# DELA_EPROMMER_II.net
KiCad netlist of a schematic drawn in Altium Designer
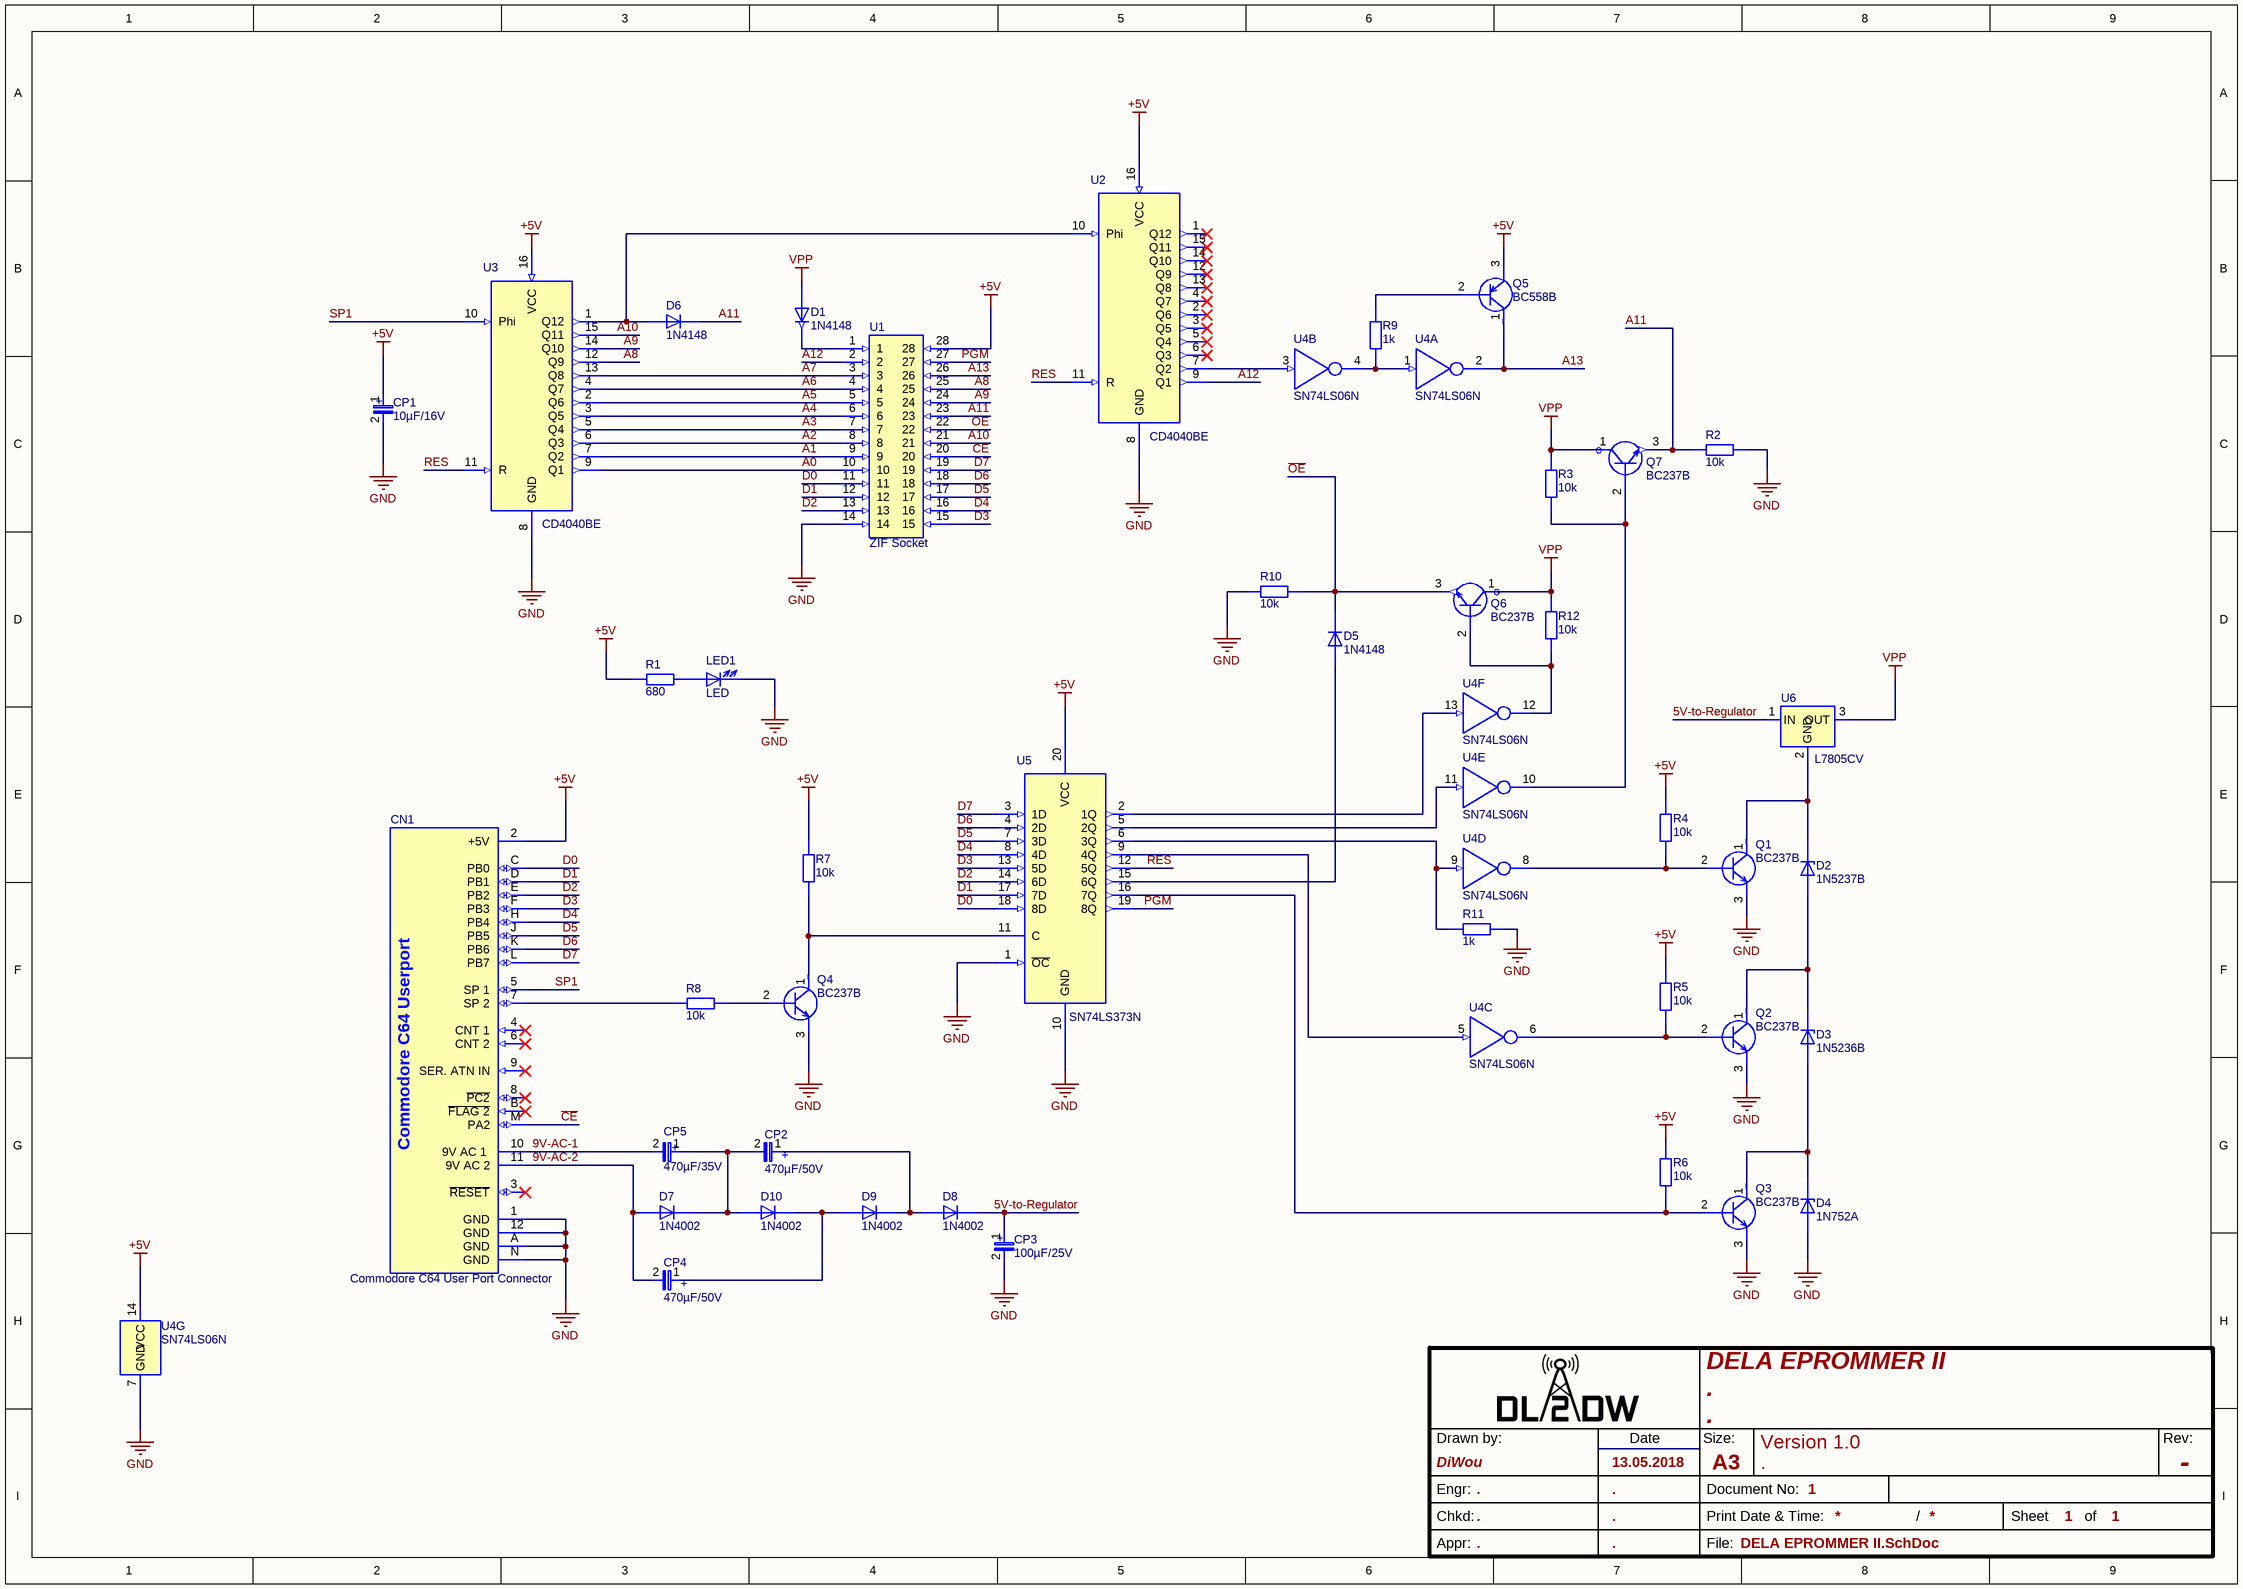
[diagram p0: DELA EPROMMER II.SchDoc]

(export (version "E")
  (design (tool "Eeschema 10.0.6"))
  (components
    (comp (ref "CN1")
      (value "Commodore C64 User Port Connector")
      (footprint "C64 User Port Connector")
      (description "Connector for soldering on the board, for connection to the user port of the C64.")
      (libsource (lib "PCB-Tech Cloud") (part "C64 Userport"))
    )
    (comp (ref "CP1")
      (value "10µF/16V")
      (footprint "CAP Elec 10µF 16V RND 150EHR100M16B")
      (description "RND 150EHR100M16B - Kondensator, 10µF, 16V, 20%, RND Components")
      (libsource (lib "") (part "Polarized Capacitor_2"))
    )
    (comp (ref "CP2")
      (value "470µF/50V")
      (footprint "CAP Elec. 470µF 50V Panasonic ECA1HHG471")
      (description "Capacitor 470 uF 50 VDC, ECA1HHG471, Panasonic Automotive & Industrial Systems")
      (fields (field (name "VOLTAGE") "50V") (field (name "TOLERANCE") "20%"))
      (libsource (lib "PCB-Tech Cloud") (part "Polarized Capacitor"))
    )
    (comp (ref "CP3")
      (value "100µF/25V")
      (footprint "CAP Elec 100µF 25V Panasonic ECA1EHG101")
      (description "Capacitor 100 uF 25 VDC, ECA1EHG101, Panasonic Automotive & Industrial Systems")
      (fields (field (name "TOLERANCE") "20%") (field (name "VOLTAGE") "25V"))
      (libsource (lib "") (part "Polarized Capacitor_2"))
    )
    (comp (ref "CP4")
      (value "470µF/50V")
      (footprint "CAP Elec. 470µF 50V Panasonic ECA1HHG471")
      (description "Capacitor 470 uF 50 VDC, ECA1HHG471, Panasonic Automotive & Industrial Systems")
      (fields (field (name "VOLTAGE") "50V") (field (name "TOLERANCE") "20%"))
      (libsource (lib "PCB-Tech Cloud") (part "Polarized Capacitor"))
    )
    (comp (ref "CP5")
      (value "470µF/35V")
      (footprint "CAP Elec 470µF 35V Panasonic ECA1VHG471")
      (fields (field (name "TOLERANCE") "20%") (field (name "VOLTAGE") "35V"))
      (libsource (lib "") (part "Polarized Capacitor_1"))
    )
    (comp (ref "D1")
      (value "1N4148")
      (footprint "1N4148 P=5.08mm")
      (description "NEXPERIA - 1N4148 - DIODE, 1N4148 AMMO-BOX 10K")
      (fields (field (name "VOLTAGE") "100V"))
      (libsource (lib "PCB-Tech Cloud") (part "Diode Standard"))
    )
    (comp (ref "D2")
      (value "1N5237B")
      (footprint "1N5237B  P=5.08mm")
      (fields (field (name "TOLERANCE") "5%"))
      (libsource (lib "PCB-Tech Cloud") (part "Zener Diode"))
    )
    (comp (ref "D3")
      (value "1N5236B")
      (footprint "1N5236B  P=5.08mm")
      (fields (field (name "TOLERANCE") "5%"))
      (libsource (lib "PCB-Tech Cloud") (part "Zener Diode"))
    )
    (comp (ref "D4")
      (value "1N752A")
      (footprint "1N752A P=5.08mm")
      (description "Zener Diode 5.6V 1/2 Watt 5% Do-35 Case")
      (libsource (lib "PCB-Tech Cloud") (part "Zener Diode"))
    )
    (comp (ref "D5")
      (value "1N4148")
      (footprint "1N4148 P=5.08mm")
      (description "NEXPERIA - 1N4148 - DIODE, 1N4148 AMMO-BOX 10K")
      (fields (field (name "VOLTAGE") "100V"))
      (libsource (lib "PCB-Tech Cloud") (part "Diode Standard"))
    )
    (comp (ref "D6")
      (value "1N4148")
      (footprint "1N4148 P=5.08mm")
      (description "NEXPERIA - 1N4148 - DIODE, 1N4148 AMMO-BOX 10K")
      (fields (field (name "VOLTAGE") "100V"))
      (libsource (lib "PCB-Tech Cloud") (part "Diode Standard"))
    )
    (comp (ref "D7")
      (value "1N4002")
      (footprint "1N4002 P=7.62mm")
      (description "DIODE GEN PURP 100V 1A DO41")
      (libsource (lib "PCB-Tech Cloud") (part "Diode Standard"))
    )
    (comp (ref "D8")
      (value "1N4002")
      (footprint "1N4002 P=7.62mm")
      (description "DIODE GEN PURP 100V 1A DO41")
      (libsource (lib "PCB-Tech Cloud") (part "Diode Standard"))
    )
    (comp (ref "D9")
      (value "1N4002")
      (footprint "1N4002 P=7.62mm")
      (description "DIODE GEN PURP 100V 1A DO41")
      (libsource (lib "PCB-Tech Cloud") (part "Diode Standard"))
    )
    (comp (ref "D10")
      (value "1N4002")
      (footprint "1N4002 P=7.62mm")
      (description "DIODE GEN PURP 100V 1A DO41")
      (libsource (lib "PCB-Tech Cloud") (part "Diode Standard"))
    )
    (comp (ref "LED1")
      (value "LED")
      (footprint "LED 3mm Red Straight")
      (description "WURTH ELEKTRONIK   151033RS03000   LED, 3MM,  RED, 2600MCD, 621NM")
      (libsource (lib "PCB-Tech Cloud") (part "LED Standard"))
    )
    (comp (ref "Q1")
      (value "BC237B")
      (footprint "BC237")
      (libsource (lib "PCB-Tech Cloud") (part "Transistor NPN CBE"))
    )
    (comp (ref "Q2")
      (value "BC237B")
      (footprint "BC237")
      (libsource (lib "PCB-Tech Cloud") (part "Transistor NPN CBE"))
    )
    (comp (ref "Q3")
      (value "BC237B")
      (footprint "BC237")
      (libsource (lib "PCB-Tech Cloud") (part "Transistor NPN CBE"))
    )
    (comp (ref "Q4")
      (value "BC237B")
      (footprint "BC237")
      (libsource (lib "PCB-Tech Cloud") (part "Transistor NPN CBE"))
    )
    (comp (ref "Q5")
      (value "BC558B")
      (footprint "BC558B")
      (libsource (lib "PCB-Tech Cloud") (part "Transistor PNP CBE"))
    )
    (comp (ref "Q6")
      (value "BC237B")
      (footprint "BC237")
      (libsource (lib "PCB-Tech Cloud") (part "Transistor NPN CBE"))
    )
    (comp (ref "Q7")
      (value "BC237B")
      (footprint "BC237")
      (libsource (lib "PCB-Tech Cloud") (part "Transistor NPN CBE"))
    )
    (comp (ref "R1")
      (value "680")
      (footprint "680 kOhm R Axial DIN0207 L6.3mm D2.5mm P7.62mm Horizontal")
      (description "Res 680K Ohm 1/4W 5% Axial")
      (fields (field (name "TOLERANCE") "5%"))
      (libsource (lib "PCB-Tech Cloud") (part "Resistor"))
    )
    (comp (ref "R2")
      (value "10k")
      (footprint "10 kOhm R Axial DIN0207 L6.3mm D2.5mm P7.62mm Horizontal")
      (description "RES 10K OHM 1/4W 5% AXIAL")
      (fields (field (name "TOLERANCE") "5%"))
      (libsource (lib "PCB-Tech Cloud") (part "Resistor"))
    )
    (comp (ref "R3")
      (value "10k")
      (footprint "10 kOhm R Axial DIN0207 L6.3mm D2.5mm P7.62mm Horizontal")
      (description "RES 10K OHM 1/4W 5% AXIAL")
      (fields (field (name "TOLERANCE") "5%"))
      (libsource (lib "PCB-Tech Cloud") (part "Resistor"))
    )
    (comp (ref "R4")
      (value "10k")
      (footprint "10 kOhm R Axial DIN0207 L6.3mm D2.5mm P7.62mm Horizontal")
      (description "RES 10K OHM 1/4W 5% AXIAL")
      (fields (field (name "TOLERANCE") "5%"))
      (libsource (lib "PCB-Tech Cloud") (part "Resistor"))
    )
    (comp (ref "R5")
      (value "10k")
      (footprint "10 kOhm R Axial DIN0207 L6.3mm D2.5mm P7.62mm Horizontal")
      (description "RES 10K OHM 1/4W 5% AXIAL")
      (fields (field (name "TOLERANCE") "5%"))
      (libsource (lib "PCB-Tech Cloud") (part "Resistor"))
    )
    (comp (ref "R6")
      (value "10k")
      (footprint "10 kOhm R Axial DIN0207 L6.3mm D2.5mm P7.62mm Horizontal")
      (description "RES 10K OHM 1/4W 5% AXIAL")
      (fields (field (name "TOLERANCE") "5%"))
      (libsource (lib "PCB-Tech Cloud") (part "Resistor"))
    )
    (comp (ref "R7")
      (value "10k")
      (footprint "10 kOhm R Axial DIN0207 L6.3mm D2.5mm P7.62mm Horizontal")
      (description "RES 10K OHM 1/4W 5% AXIAL")
      (fields (field (name "TOLERANCE") "5%"))
      (libsource (lib "PCB-Tech Cloud") (part "Resistor"))
    )
    (comp (ref "R8")
      (value "10k")
      (footprint "10 kOhm R Axial DIN0207 L6.3mm D2.5mm P7.62mm Horizontal")
      (description "RES 10K OHM 1/4W 5% AXIAL")
      (fields (field (name "TOLERANCE") "5%"))
      (libsource (lib "PCB-Tech Cloud") (part "Resistor"))
    )
    (comp (ref "R9")
      (value "1k")
      (footprint "1,0 kOhm R Axial DIN0207 L6.3mm D2.5mm P7.62mm Horizontal")
      (description "RES 1K OHM 1/4W 5% AXIAL")
      (fields (field (name "TOLERANCE") "5%"))
      (libsource (lib "PCB-Tech Cloud") (part "Resistor"))
    )
    (comp (ref "R10")
      (value "10k")
      (footprint "10 kOhm R Axial DIN0207 L6.3mm D2.5mm P7.62mm Horizontal")
      (description "RES 10K OHM 1/4W 5% AXIAL")
      (fields (field (name "TOLERANCE") "5%"))
      (libsource (lib "PCB-Tech Cloud") (part "Resistor"))
    )
    (comp (ref "R11")
      (value "1k")
      (footprint "1,0 kOhm R Axial DIN0207 L6.3mm D2.5mm P7.62mm Horizontal")
      (description "RES 1K OHM 1/4W 5% AXIAL")
      (fields (field (name "TOLERANCE") "5%"))
      (libsource (lib "PCB-Tech Cloud") (part "Resistor"))
    )
    (comp (ref "R12")
      (value "10k")
      (footprint "10 kOhm R Axial DIN0207 L6.3mm D2.5mm P7.62mm Horizontal")
      (description "RES 10K OHM 1/4W 5% AXIAL")
      (fields (field (name "TOLERANCE") "5%"))
      (libsource (lib "PCB-Tech Cloud") (part "Resistor"))
    )
    (comp (ref "U1")
      (value "ZIF Socket")
      (footprint "ZIF Socket Textool 28pos P=15.24mm")
      (description "CONN IC DIP SOCKET ZIF 28POS GLD")
      (libsource (lib "PCB-Tech Cloud") (part "ZIF Socket Textool 28pos"))
    )
    (comp (ref "U2")
      (value "CD4040BE")
      (footprint "CD4040BE with Socket")
      (description "Counter/Divider Single 12-Bit Binary UP 16-Pin PDIP Tube")
      (libsource (lib "PCB-Tech Cloud") (part "CD4040BE"))
    )
    (comp (ref "U3")
      (value "CD4040BE")
      (footprint "CD4040BE with Socket")
      (description "Counter/Divider Single 12-Bit Binary UP 16-Pin PDIP Tube")
      (libsource (lib "PCB-Tech Cloud") (part "CD4040BE"))
    )
    (comp (ref "U4")
      (value "SN74LS06N")
      (footprint "SN74LS06N with Socket")
      (description "IC INVERTER OPEN COL 6CH 14DIP")
      (libsource (lib "") (part "74xx06_1"))
    )
    (comp (ref "U5")
      (value "SN74LS373N")
      (footprint "SN74LS373N with Socket")
      (description "Latch Transparent 3-ST 8-CH D-Type 20-Pin PDIP Tube")
      (libsource (lib "PCB-Tech Cloud") (part "74xx373"))
    )
    (comp (ref "U6")
      (value "L7805CV")
      (footprint "L 7805 CV")
      (description "STMICROELECTRONICS - L7806CV - LINEAR VOLTAGE REGULATOR 6V TO-220-3")
      (fields (field (name "TOLERANCE") "5%"))
      (libsource (lib "PCB-Tech Cloud") (part "L7805CV"))
    )
  )
  (nets
    (net (code "1") (name "+5V") (class "Default")
      (node (ref "CN1") (pin "2") (pinfunction "+5V_2") (pintype "power_in"))
      (node (ref "CP1") (pin "1") (pinfunction "1_1") (pintype "passive"))
      (node (ref "Q5") (pin "3") (pinfunction "3_3") (pintype "passive"))
      (node (ref "R1") (pin "2") (pinfunction "2_2") (pintype "passive"))
      (node (ref "R4") (pin "1") (pinfunction "1_1") (pintype "passive"))
      (node (ref "R5") (pin "1") (pinfunction "1_1") (pintype "passive"))
      (node (ref "R6") (pin "1") (pinfunction "1_1") (pintype "passive"))
      (node (ref "R7") (pin "1") (pinfunction "1_1") (pintype "passive"))
      (node (ref "U1") (pin "28") (pinfunction "28_28") (pintype "input"))
      (node (ref "U2") (pin "16") (pinfunction "VCC_16") (pintype "input"))
      (node (ref "U3") (pin "16") (pinfunction "VCC_16") (pintype "input"))
      (node (ref "U4") (pin "14") (pinfunction "VCC_14") (pintype "power_in"))
      (node (ref "U5") (pin "20") (pinfunction "VCC_20") (pintype "power_in"))
    )
    (net (code "2") (name "/5V-to-Regulator") (class "Default")
      (node (ref "CP3") (pin "1") (pinfunction "1_1") (pintype "passive"))
      (node (ref "D8") (pin "1") (pinfunction "1_1") (pintype "passive"))
      (node (ref "U6") (pin "1") (pinfunction "IN_1") (pintype "power_in"))
    )
    (net (code "3") (name "/9V-AC-1") (class "Default")
      (node (ref "CN1") (pin "10") (pinfunction "9V_AC_1_10") (pintype "power_in"))
      (node (ref "CP5") (pin "2") (pinfunction "2_2") (pintype "passive"))
    )
    (net (code "4") (name "/9V-AC-2") (class "Default")
      (node (ref "CN1") (pin "11") (pinfunction "9V_AC_2_11") (pintype "power_in"))
      (node (ref "CP4") (pin "2") (pinfunction "2_2") (pintype "passive"))
      (node (ref "D7") (pin "2") (pinfunction "2_2") (pintype "passive"))
    )
    (net (code "5") (name "/A0") (class "Default")
      (node (ref "U1") (pin "10") (pinfunction "10_10") (pintype "input"))
      (node (ref "U3") (pin "9") (pinfunction "Q1_9") (pintype "output"))
    )
    (net (code "6") (name "/A1") (class "Default")
      (node (ref "U1") (pin "9") (pinfunction "9_9") (pintype "input"))
      (node (ref "U3") (pin "7") (pinfunction "Q2_7") (pintype "output"))
    )
    (net (code "7") (name "/A2") (class "Default")
      (node (ref "U1") (pin "8") (pinfunction "8_8") (pintype "input"))
      (node (ref "U3") (pin "6") (pinfunction "Q3_6") (pintype "output"))
    )
    (net (code "8") (name "/A3") (class "Default")
      (node (ref "U1") (pin "7") (pinfunction "7_7") (pintype "input"))
      (node (ref "U3") (pin "5") (pinfunction "Q4_5") (pintype "output"))
    )
    (net (code "9") (name "/A4") (class "Default")
      (node (ref "U1") (pin "6") (pinfunction "6_6") (pintype "input"))
      (node (ref "U3") (pin "3") (pinfunction "Q5_3") (pintype "output"))
    )
    (net (code "10") (name "/A5") (class "Default")
      (node (ref "U1") (pin "5") (pinfunction "5_5") (pintype "input"))
      (node (ref "U3") (pin "2") (pinfunction "Q6_2") (pintype "output"))
    )
    (net (code "11") (name "/A6") (class "Default")
      (node (ref "U1") (pin "4") (pinfunction "4_4") (pintype "input"))
      (node (ref "U3") (pin "4") (pinfunction "Q7_4") (pintype "output"))
    )
    (net (code "12") (name "/A7") (class "Default")
      (node (ref "U1") (pin "3") (pinfunction "3_3") (pintype "input"))
      (node (ref "U3") (pin "13") (pinfunction "Q8_13") (pintype "output"))
    )
    (net (code "13") (name "/A8") (class "Default")
      (node (ref "U1") (pin "25") (pinfunction "25_25") (pintype "input"))
      (node (ref "U3") (pin "12") (pinfunction "Q9_12") (pintype "output"))
    )
    (net (code "14") (name "/A9") (class "Default")
      (node (ref "U1") (pin "24") (pinfunction "24_24") (pintype "input"))
      (node (ref "U3") (pin "14") (pinfunction "Q10_14") (pintype "output"))
    )
    (net (code "15") (name "/A10") (class "Default")
      (node (ref "U1") (pin "21") (pinfunction "21_21") (pintype "input"))
      (node (ref "U3") (pin "15") (pinfunction "Q11_15") (pintype "output"))
    )
    (net (code "16") (name "/A11") (class "Default")
      (node (ref "D6") (pin "1") (pinfunction "1_1") (pintype "passive"))
      (node (ref "Q7") (pin "3") (pinfunction "3_3") (pintype "passive"))
      (node (ref "R2") (pin "2") (pinfunction "2_2") (pintype "passive"))
      (node (ref "U1") (pin "23") (pinfunction "23_23") (pintype "input"))
    )
    (net (code "17") (name "/A12") (class "Default")
      (node (ref "U1") (pin "2") (pinfunction "2_2") (pintype "input"))
      (node (ref "U2") (pin "9") (pinfunction "Q1_9") (pintype "output"))
    )
    (net (code "18") (name "/A13") (class "Default")
      (node (ref "Q5") (pin "1") (pinfunction "1_1") (pintype "passive"))
      (node (ref "U1") (pin "26") (pinfunction "26_26") (pintype "input"))
      (node (ref "U4") (pin "2") (pinfunction "1Y_2") (pintype "open_collector"))
    )
    (net (code "19") (name "/D0") (class "Default")
      (node (ref "CN1") (pin "C") (pinfunction "PB0_C") (pintype "bidirectional"))
      (node (ref "U1") (pin "11") (pinfunction "11_11") (pintype "input"))
      (node (ref "U5") (pin "18") (pinfunction "8D_18") (pintype "input"))
    )
    (net (code "20") (name "/D1") (class "Default")
      (node (ref "CN1") (pin "D") (pinfunction "PB1_D") (pintype "bidirectional"))
      (node (ref "U1") (pin "12") (pinfunction "12_12") (pintype "input"))
      (node (ref "U5") (pin "17") (pinfunction "7D_17") (pintype "input"))
    )
    (net (code "21") (name "/D2") (class "Default")
      (node (ref "CN1") (pin "E") (pinfunction "PB2_E") (pintype "bidirectional"))
      (node (ref "U1") (pin "13") (pinfunction "13_13") (pintype "input"))
      (node (ref "U5") (pin "14") (pinfunction "6D_14") (pintype "input"))
    )
    (net (code "22") (name "/D3") (class "Default")
      (node (ref "CN1") (pin "F") (pinfunction "PB3_F") (pintype "bidirectional"))
      (node (ref "U1") (pin "15") (pinfunction "15_15") (pintype "input"))
      (node (ref "U5") (pin "13") (pinfunction "5D_13") (pintype "input"))
    )
    (net (code "23") (name "/D4") (class "Default")
      (node (ref "CN1") (pin "H") (pinfunction "PB4_H") (pintype "bidirectional"))
      (node (ref "U1") (pin "16") (pinfunction "16_16") (pintype "input"))
      (node (ref "U5") (pin "8") (pinfunction "4D_8") (pintype "input"))
    )
    (net (code "24") (name "/D5") (class "Default")
      (node (ref "CN1") (pin "J") (pinfunction "PB5_J") (pintype "bidirectional"))
      (node (ref "U1") (pin "17") (pinfunction "17_17") (pintype "input"))
      (node (ref "U5") (pin "7") (pinfunction "3D_7") (pintype "input"))
    )
    (net (code "25") (name "/D6") (class "Default")
      (node (ref "CN1") (pin "K") (pinfunction "PB6_K") (pintype "bidirectional"))
      (node (ref "U1") (pin "18") (pinfunction "18_18") (pintype "input"))
      (node (ref "U5") (pin "4") (pinfunction "2D_4") (pintype "input"))
    )
    (net (code "26") (name "/D7") (class "Default")
      (node (ref "CN1") (pin "L") (pinfunction "PB7_L") (pintype "bidirectional"))
      (node (ref "U1") (pin "19") (pinfunction "19_19") (pintype "input"))
      (node (ref "U5") (pin "3") (pinfunction "1D_3") (pintype "input"))
    )
    (net (code "27") (name "/RES") (class "Default")
      (node (ref "U2") (pin "11") (pinfunction "R_11") (pintype "input"))
      (node (ref "U3") (pin "11") (pinfunction "R_11") (pintype "input"))
      (node (ref "U5") (pin "12") (pinfunction "5Q_12") (pintype "output"))
    )
    (net (code "28") (name "/SP1") (class "Default")
      (node (ref "CN1") (pin "5") (pinfunction "SP_1_5") (pintype "bidirectional"))
      (node (ref "U3") (pin "10") (pinfunction "Phi_10") (pintype "input"))
    )
    (net (code "29") (name "/~{CE}") (class "Default")
      (node (ref "CN1") (pin "M") (pinfunction "PA2_M") (pintype "bidirectional"))
      (node (ref "U1") (pin "20") (pinfunction "20_20") (pintype "input"))
    )
    (net (code "30") (name "/~{OE}") (class "Default")
      (node (ref "D5") (pin "1") (pinfunction "1_1") (pintype "passive"))
      (node (ref "Q6") (pin "3") (pinfunction "3_3") (pintype "passive"))
      (node (ref "R10") (pin "1") (pinfunction "1_1") (pintype "passive"))
      (node (ref "U1") (pin "22") (pinfunction "22_22") (pintype "input"))
    )
    (net (code "31") (name "/~{PGM}") (class "Default")
      (node (ref "U1") (pin "27") (pinfunction "27_27") (pintype "input"))
      (node (ref "U5") (pin "19") (pinfunction "8Q_19") (pintype "output"))
    )
    (net (code "32") (name "GND") (class "Default")
      (node (ref "CN1") (pin "1") (pinfunction "GND_1") (pintype "passive"))
      (node (ref "CN1") (pin "12") (pinfunction "GND_12") (pintype "passive"))
      (node (ref "CN1") (pin "A") (pinfunction "GND_A") (pintype "passive"))
      (node (ref "CN1") (pin "N") (pinfunction "GND_N") (pintype "passive"))
      (node (ref "CP1") (pin "2") (pinfunction "2_2") (pintype "passive"))
      (node (ref "CP3") (pin "2") (pinfunction "2_2") (pintype "passive"))
      (node (ref "D4") (pin "2") (pinfunction "2_2") (pintype "passive"))
      (node (ref "LED1") (pin "1") (pinfunction "1_1") (pintype "passive"))
      (node (ref "Q1") (pin "3") (pinfunction "3_3") (pintype "passive"))
      (node (ref "Q2") (pin "3") (pinfunction "3_3") (pintype "passive"))
      (node (ref "Q3") (pin "3") (pinfunction "3_3") (pintype "passive"))
      (node (ref "Q4") (pin "3") (pinfunction "3_3") (pintype "passive"))
      (node (ref "R10") (pin "2") (pinfunction "2_2") (pintype "passive"))
      (node (ref "R11") (pin "2") (pinfunction "2_2") (pintype "passive"))
      (node (ref "R2") (pin "1") (pinfunction "1_1") (pintype "passive"))
      (node (ref "U1") (pin "14") (pinfunction "14_14") (pintype "input"))
      (node (ref "U2") (pin "8") (pinfunction "GND_8") (pintype "power_in"))
      (node (ref "U3") (pin "8") (pinfunction "GND_8") (pintype "power_in"))
      (node (ref "U4") (pin "7") (pinfunction "GND_7") (pintype "passive"))
      (node (ref "U5") (pin "1") (pinfunction "~{OC}_1") (pintype "input"))
      (node (ref "U5") (pin "10") (pinfunction "GND_10") (pintype "power_in"))
    )
    (net (code "33") (name "Net-(CN1-SP_2)") (class "Default")
      (node (ref "CN1") (pin "7") (pinfunction "SP_2_7") (pintype "bidirectional"))
      (node (ref "R8") (pin "1") (pinfunction "1_1") (pintype "passive"))
    )
    (net (code "34") (name "Net-(CP2-Pad1)") (class "Default")
      (node (ref "CP2") (pin "1") (pinfunction "1_1") (pintype "passive"))
      (node (ref "D8") (pin "2") (pinfunction "2_2") (pintype "passive"))
      (node (ref "D9") (pin "1") (pinfunction "1_1") (pintype "passive"))
    )
    (net (code "35") (name "Net-(CP2-Pad2)") (class "Default")
      (node (ref "CP2") (pin "2") (pinfunction "2_2") (pintype "passive"))
      (node (ref "CP5") (pin "1") (pinfunction "1_1") (pintype "passive"))
      (node (ref "D10") (pin "2") (pinfunction "2_2") (pintype "passive"))
      (node (ref "D7") (pin "1") (pinfunction "1_1") (pintype "passive"))
    )
    (net (code "36") (name "Net-(CP4-Pad1)") (class "Default")
      (node (ref "CP4") (pin "1") (pinfunction "1_1") (pintype "passive"))
      (node (ref "D10") (pin "1") (pinfunction "1_1") (pintype "passive"))
      (node (ref "D9") (pin "2") (pinfunction "2_2") (pintype "passive"))
    )
    (net (code "37") (name "Net-(D1-Pad1)") (class "Default")
      (node (ref "D1") (pin "1") (pinfunction "1_1") (pintype "passive"))
      (node (ref "U1") (pin "1") (pinfunction "1_1") (pintype "input"))
    )
    (net (code "38") (name "Net-(D2-Pad2)") (class "Default")
      (node (ref "D2") (pin "2") (pinfunction "2_2") (pintype "passive"))
      (node (ref "D3") (pin "1") (pinfunction "1_1") (pintype "passive"))
      (node (ref "Q2") (pin "1") (pinfunction "1_1") (pintype "passive"))
    )
    (net (code "39") (name "Net-(D3-Pad2)") (class "Default")
      (node (ref "D3") (pin "2") (pinfunction "2_2") (pintype "passive"))
      (node (ref "D4") (pin "1") (pinfunction "1_1") (pintype "passive"))
      (node (ref "Q3") (pin "1") (pinfunction "1_1") (pintype "passive"))
    )
    (net (code "40") (name "Net-(LED1-Pad2)") (class "Default")
      (node (ref "LED1") (pin "2") (pinfunction "2_2") (pintype "passive"))
      (node (ref "R1") (pin "1") (pinfunction "1_1") (pintype "passive"))
    )
    (net (code "41") (name "Net-(Q4-Pad2)") (class "Default")
      (node (ref "Q4") (pin "2") (pinfunction "2_2") (pintype "passive"))
      (node (ref "R8") (pin "2") (pinfunction "2_2") (pintype "passive"))
    )
    (net (code "42") (name "Net-(Q5-Pad2)") (class "Default")
      (node (ref "Q5") (pin "2") (pinfunction "2_2") (pintype "passive"))
      (node (ref "R9") (pin "1") (pinfunction "1_1") (pintype "passive"))
    )
    (net (code "43") (name "Net-(U2-Phi)") (class "Default")
      (node (ref "D6") (pin "2") (pinfunction "2_2") (pintype "passive"))
      (node (ref "U2") (pin "10") (pinfunction "Phi_10") (pintype "input"))
      (node (ref "U3") (pin "1") (pinfunction "Q12_1") (pintype "output"))
    )
    (net (code "44") (name "Net-(U2-Q2)") (class "Default")
      (node (ref "U2") (pin "7") (pinfunction "Q2_7") (pintype "output"))
      (node (ref "U4") (pin "3") (pinfunction "2A_3") (pintype "input"))
    )
    (net (code "45") (name "Net-(U4A-1A)") (class "Default")
      (node (ref "R9") (pin "2") (pinfunction "2_2") (pintype "passive"))
      (node (ref "U4") (pin "1") (pinfunction "1A_1") (pintype "input"))
      (node (ref "U4") (pin "4") (pinfunction "2Y_4") (pintype "open_collector"))
    )
    (net (code "46") (name "Net-(U4C-3A)") (class "Default")
      (node (ref "U4") (pin "5") (pinfunction "3A_5") (pintype "input"))
      (node (ref "U5") (pin "9") (pinfunction "4Q_9") (pintype "output"))
    )
    (net (code "47") (name "Net-(U4C-3Y)") (class "Default")
      (node (ref "Q2") (pin "2") (pinfunction "2_2") (pintype "passive"))
      (node (ref "R5") (pin "2") (pinfunction "2_2") (pintype "passive"))
      (node (ref "U4") (pin "6") (pinfunction "3Y_6") (pintype "open_collector"))
    )
    (net (code "48") (name "Net-(U4D-4A)") (class "Default")
      (node (ref "R11") (pin "1") (pinfunction "1_1") (pintype "passive"))
      (node (ref "U4") (pin "9") (pinfunction "4A_9") (pintype "input"))
      (node (ref "U5") (pin "6") (pinfunction "3Q_6") (pintype "output"))
    )
    (net (code "49") (name "Net-(U4D-4Y)") (class "Default")
      (node (ref "Q1") (pin "2") (pinfunction "2_2") (pintype "passive"))
      (node (ref "R4") (pin "2") (pinfunction "2_2") (pintype "passive"))
      (node (ref "U4") (pin "8") (pinfunction "4Y_8") (pintype "open_collector"))
    )
    (net (code "50") (name "Net-(U4E-5A)") (class "Default")
      (node (ref "U4") (pin "11") (pinfunction "5A_11") (pintype "input"))
      (node (ref "U5") (pin "5") (pinfunction "2Q_5") (pintype "output"))
    )
    (net (code "51") (name "Net-(U4E-5Y)") (class "Default")
      (node (ref "Q7") (pin "2") (pinfunction "2_2") (pintype "passive"))
      (node (ref "R3") (pin "2") (pinfunction "2_2") (pintype "passive"))
      (node (ref "U4") (pin "10") (pinfunction "5Y_10") (pintype "open_collector"))
    )
    (net (code "52") (name "Net-(U4F-6A)") (class "Default")
      (node (ref "U4") (pin "13") (pinfunction "6A_13") (pintype "input"))
      (node (ref "U5") (pin "2") (pinfunction "1Q_2") (pintype "output"))
    )
    (net (code "53") (name "Net-(U4F-6Y)") (class "Default")
      (node (ref "Q6") (pin "2") (pinfunction "2_2") (pintype "passive"))
      (node (ref "R12") (pin "2") (pinfunction "2_2") (pintype "passive"))
      (node (ref "U4") (pin "12") (pinfunction "6Y_12") (pintype "open_collector"))
    )
    (net (code "54") (name "Net-(U5-6Q)") (class "Default")
      (node (ref "D5") (pin "2") (pinfunction "2_2") (pintype "passive"))
      (node (ref "U5") (pin "15") (pinfunction "6Q_15") (pintype "output"))
    )
    (net (code "55") (name "Net-(U5-7Q)") (class "Default")
      (node (ref "Q3") (pin "2") (pinfunction "2_2") (pintype "passive"))
      (node (ref "R6") (pin "2") (pinfunction "2_2") (pintype "passive"))
      (node (ref "U5") (pin "16") (pinfunction "7Q_16") (pintype "output"))
    )
    (net (code "56") (name "Net-(U5-C)") (class "Default")
      (node (ref "Q4") (pin "1") (pinfunction "1_1") (pintype "passive"))
      (node (ref "R7") (pin "2") (pinfunction "2_2") (pintype "passive"))
      (node (ref "U5") (pin "11") (pinfunction "C_11") (pintype "passive"))
    )
    (net (code "57") (name "Net-(U6-GND)") (class "Default")
      (node (ref "D2") (pin "1") (pinfunction "1_1") (pintype "passive"))
      (node (ref "Q1") (pin "1") (pinfunction "1_1") (pintype "passive"))
      (node (ref "U6") (pin "2") (pinfunction "GND_2") (pintype "passive"))
    )
    (net (code "58") (name "N{slash}C") (class "Default")
      (node (ref "U6") (pin "4") (pinfunction "N/C_4") (pintype "power_in"))
    )
    (net (code "59") (name "VPP") (class "Default")
      (node (ref "D1") (pin "2") (pinfunction "2_2") (pintype "passive"))
      (node (ref "Q6") (pin "1") (pinfunction "1_1") (pintype "passive"))
      (node (ref "Q7") (pin "1") (pinfunction "1_1") (pintype "passive"))
      (node (ref "R12") (pin "1") (pinfunction "1_1") (pintype "passive"))
      (node (ref "R3") (pin "1") (pinfunction "1_1") (pintype "passive"))
      (node (ref "U6") (pin "3") (pinfunction "OUT_3") (pintype "power_in"))
    )
    (net (code "60") (name "unconnected-(CN1-CNT_1-Pad4)") (class "Default")
      (node (ref "CN1") (pin "4") (pinfunction "CNT_1_4") (pintype "input+no_connect"))
    )
    (net (code "61") (name "unconnected-(CN1-CNT_2-Pad6)") (class "Default")
      (node (ref "CN1") (pin "6") (pinfunction "CNT_2_6") (pintype "input+no_connect"))
    )
    (net (code "62") (name "unconnected-(CN1-SER._ATN_IN-Pad9)") (class "Default")
      (node (ref "CN1") (pin "9") (pinfunction "SER._ATN_IN_9") (pintype "input+no_connect"))
    )
    (net (code "63") (name "unconnected-(CN1-~{FLAG_2}-PadB)") (class "Default")
      (node (ref "CN1") (pin "B") (pinfunction "~{FLAG_2}_B") (pintype "input+no_connect"))
    )
    (net (code "64") (name "unconnected-(CN1-~{PC2}-Pad8)") (class "Default")
      (node (ref "CN1") (pin "8") (pinfunction "~{PC2}_8") (pintype "bidirectional+no_connect"))
    )
    (net (code "65") (name "unconnected-(CN1-~{RESET}-Pad3)") (class "Default")
      (node (ref "CN1") (pin "3") (pinfunction "~{RESET}_3") (pintype "bidirectional+no_connect"))
    )
    (net (code "66") (name "unconnected-(U2-Q3-Pad6)") (class "Default")
      (node (ref "U2") (pin "6") (pinfunction "Q3_6") (pintype "output+no_connect"))
    )
    (net (code "67") (name "unconnected-(U2-Q4-Pad5)") (class "Default")
      (node (ref "U2") (pin "5") (pinfunction "Q4_5") (pintype "output+no_connect"))
    )
    (net (code "68") (name "unconnected-(U2-Q5-Pad3)") (class "Default")
      (node (ref "U2") (pin "3") (pinfunction "Q5_3") (pintype "output+no_connect"))
    )
    (net (code "69") (name "unconnected-(U2-Q6-Pad2)") (class "Default")
      (node (ref "U2") (pin "2") (pinfunction "Q6_2") (pintype "output+no_connect"))
    )
    (net (code "70") (name "unconnected-(U2-Q7-Pad4)") (class "Default")
      (node (ref "U2") (pin "4") (pinfunction "Q7_4") (pintype "output+no_connect"))
    )
    (net (code "71") (name "unconnected-(U2-Q8-Pad13)") (class "Default")
      (node (ref "U2") (pin "13") (pinfunction "Q8_13") (pintype "output+no_connect"))
    )
    (net (code "72") (name "unconnected-(U2-Q9-Pad12)") (class "Default")
      (node (ref "U2") (pin "12") (pinfunction "Q9_12") (pintype "output+no_connect"))
    )
    (net (code "73") (name "unconnected-(U2-Q10-Pad14)") (class "Default")
      (node (ref "U2") (pin "14") (pinfunction "Q10_14") (pintype "output+no_connect"))
    )
    (net (code "74") (name "unconnected-(U2-Q11-Pad15)") (class "Default")
      (node (ref "U2") (pin "15") (pinfunction "Q11_15") (pintype "output+no_connect"))
    )
    (net (code "75") (name "unconnected-(U2-Q12-Pad1)") (class "Default")
      (node (ref "U2") (pin "1") (pinfunction "Q12_1") (pintype "output+no_connect"))
    )
  )
)
